# Main.net
KiCad netlist of a schematic drawn in Altium Designer
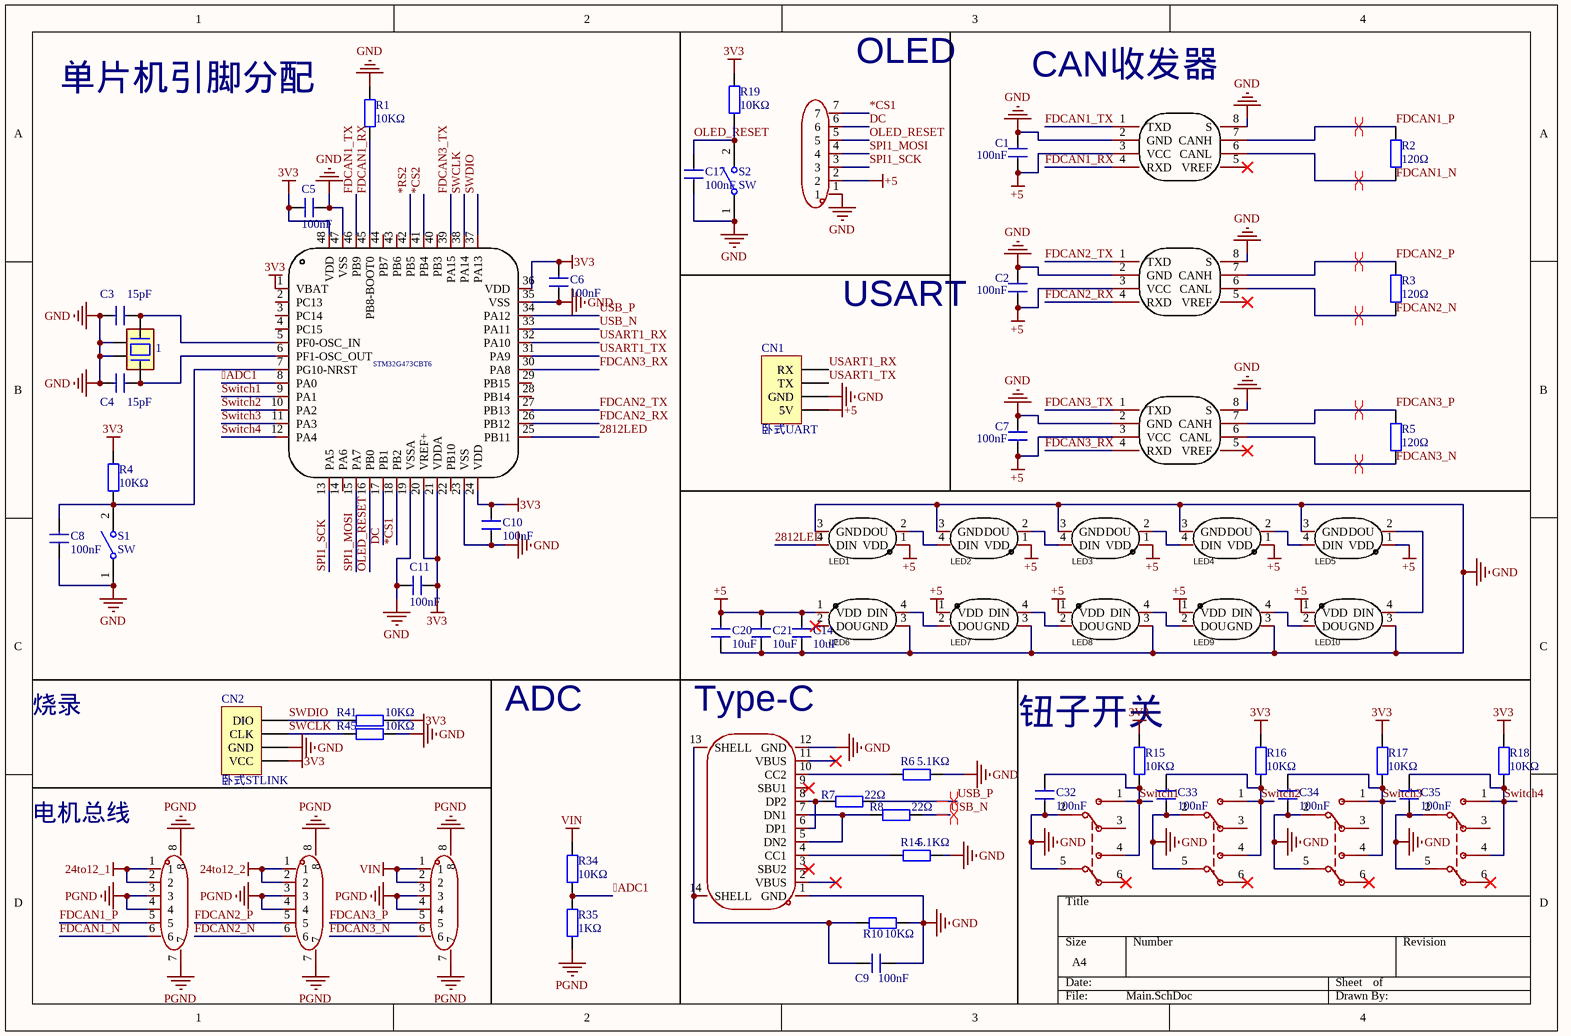
[diagram p0: Main.SchDoc]

(export (version "E")
  (design (tool "Eeschema 10.0.6"))
  (components
    (comp (ref "1")
      (value "3225贴片晶振")
      (footprint "OSC-3225-4P")
      (libsource (lib "Integrated_Library1") (part "3225贴片晶振"))
    )
    (comp (ref "C1")
      (value "100nF")
      (footprint "c0402")
      (description "贴片电容0402")
      (libsource (lib "Integrated_Library1") (part "0402贴片电容"))
    )
    (comp (ref "C2")
      (value "100nF")
      (footprint "c0402")
      (description "贴片电容0402")
      (libsource (lib "Integrated_Library1") (part "0402贴片电容"))
    )
    (comp (ref "C3")
      (value "15pF")
      (footprint "c0402")
      (description "贴片电容0402")
      (libsource (lib "Integrated_Library1") (part "0402贴片电容"))
    )
    (comp (ref "C4")
      (value "15pF")
      (footprint "c0402")
      (description "贴片电容0402")
      (libsource (lib "Integrated_Library1") (part "0402贴片电容"))
    )
    (comp (ref "C5")
      (value "100nF")
      (footprint "c0402")
      (description "贴片电容0402")
      (libsource (lib "Integrated_Library1") (part "0402贴片电容"))
    )
    (comp (ref "C6")
      (value "100nF")
      (footprint "c0402")
      (description "贴片电容0402")
      (libsource (lib "Integrated_Library1") (part "0402贴片电容"))
    )
    (comp (ref "C7")
      (value "100nF")
      (footprint "c0402")
      (description "贴片电容0402")
      (libsource (lib "Integrated_Library1") (part "0402贴片电容"))
    )
    (comp (ref "C8")
      (value "100nF")
      (footprint "c0402")
      (description "贴片电容0402")
      (libsource (lib "Integrated_Library1") (part "0402贴片电容"))
    )
    (comp (ref "C9")
      (value "100nF")
      (footprint "c0402")
      (description "贴片电容0402")
      (libsource (lib "Integrated_Library1") (part "0402贴片电容"))
    )
    (comp (ref "C10")
      (value "100nF")
      (footprint "c0402")
      (description "贴片电容0402")
      (libsource (lib "Integrated_Library1") (part "0402贴片电容"))
    )
    (comp (ref "C11")
      (value "100nF")
      (footprint "c0402")
      (description "贴片电容0402")
      (libsource (lib "Integrated_Library1") (part "0402贴片电容"))
    )
    (comp (ref "C14")
      (value "10uF")
      (footprint "1210")
      (description "1210贴片电容")
      (libsource (lib "Integrated_Library1") (part "1210贴片电容"))
    )
    (comp (ref "C17")
      (value "100nF")
      (footprint "c0402")
      (description "贴片电容0402")
      (libsource (lib "Integrated_Library1") (part "0402贴片电容"))
    )
    (comp (ref "C20")
      (value "10uF")
      (footprint "1210")
      (description "1210贴片电容")
      (libsource (lib "Integrated_Library1") (part "1210贴片电容"))
    )
    (comp (ref "C21")
      (value "10uF")
      (footprint "1210")
      (description "1210贴片电容")
      (libsource (lib "Integrated_Library1") (part "1210贴片电容"))
    )
    (comp (ref "C32")
      (value "100nF")
      (footprint "c0402")
      (description "贴片电容0402")
      (libsource (lib "Integrated_Library1") (part "0402贴片电容"))
    )
    (comp (ref "C33")
      (value "100nF")
      (footprint "c0402")
      (description "贴片电容0402")
      (libsource (lib "Integrated_Library1") (part "0402贴片电容"))
    )
    (comp (ref "C34")
      (value "100nF")
      (footprint "c0402")
      (description "贴片电容0402")
      (libsource (lib "Integrated_Library1") (part "0402贴片电容"))
    )
    (comp (ref "C35")
      (value "100nF")
      (footprint "c0402")
      (description "贴片电容0402")
      (libsource (lib "Integrated_Library1") (part "0402贴片电容"))
    )
    (comp (ref "CN1")
      (value "卧式UART")
      (footprint "CONN-SMD_4P-P1.25_GH1.25-4P")
      (libsource (lib "Integrated_Library1") (part "卧式UART"))
    )
    (comp (ref "CN2")
      (value "卧式STLINK")
      (footprint "CONN-SMD_4P-P1.25_GH1.25-4P")
      (libsource (lib "Integrated_Library1") (part "卧式STLINK"))
    )
    (comp (ref "H1")
      (value "PM254V-11-07-H85")
      (footprint "HDR-TH_7P-P2.54-V-F")
      (fields (field (name "MANUFACTURER") "XFCN(兴飞)"))
      (libsource (lib "Schlib1") (part "PM254V-11-07-H85"))
    )
    (comp (ref "LED1")
      (value "XL-5050RGBC-WS2812B")
      (footprint "LED-SMD_4P-L5.0-W5.0-BL_XL-5050RGBC")
      (description "WS2812B彩灯珠")
      (fields (field (name "MANUFACTURER") "XINGLIGHT(成兴光)"))
      (libsource (lib "RoBoMaster_AllComponent") (part "WS2812B彩灯珠"))
    )
    (comp (ref "LED2")
      (value "XL-5050RGBC-WS2812B")
      (footprint "LED-SMD_4P-L5.0-W5.0-BL_XL-5050RGBC")
      (description "WS2812B彩灯珠")
      (fields (field (name "MANUFACTURER") "XINGLIGHT(成兴光)"))
      (libsource (lib "RoBoMaster_AllComponent") (part "WS2812B彩灯珠"))
    )
    (comp (ref "LED3")
      (value "XL-5050RGBC-WS2812B")
      (footprint "LED-SMD_4P-L5.0-W5.0-BL_XL-5050RGBC")
      (description "WS2812B彩灯珠")
      (fields (field (name "MANUFACTURER") "XINGLIGHT(成兴光)"))
      (libsource (lib "RoBoMaster_AllComponent") (part "WS2812B彩灯珠"))
    )
    (comp (ref "LED4")
      (value "XL-5050RGBC-WS2812B")
      (footprint "LED-SMD_4P-L5.0-W5.0-BL_XL-5050RGBC")
      (description "WS2812B彩灯珠")
      (fields (field (name "MANUFACTURER") "XINGLIGHT(成兴光)"))
      (libsource (lib "RoBoMaster_AllComponent") (part "WS2812B彩灯珠"))
    )
    (comp (ref "LED5")
      (value "XL-5050RGBC-WS2812B")
      (footprint "LED-SMD_4P-L5.0-W5.0-BL_XL-5050RGBC")
      (description "WS2812B彩灯珠")
      (fields (field (name "MANUFACTURER") "XINGLIGHT(成兴光)"))
      (libsource (lib "RoBoMaster_AllComponent") (part "WS2812B彩灯珠"))
    )
    (comp (ref "LED6")
      (value "XL-5050RGBC-WS2812B")
      (footprint "LED-SMD_4P-L5.0-W5.0-BL_XL-5050RGBC")
      (description "WS2812B彩灯珠")
      (fields (field (name "MANUFACTURER") "XINGLIGHT(成兴光)"))
      (libsource (lib "RoBoMaster_AllComponent") (part "WS2812B彩灯珠"))
    )
    (comp (ref "LED7")
      (value "XL-5050RGBC-WS2812B")
      (footprint "LED-SMD_4P-L5.0-W5.0-BL_XL-5050RGBC")
      (description "WS2812B彩灯珠")
      (fields (field (name "MANUFACTURER") "XINGLIGHT(成兴光)"))
      (libsource (lib "RoBoMaster_AllComponent") (part "WS2812B彩灯珠"))
    )
    (comp (ref "LED8")
      (value "XL-5050RGBC-WS2812B")
      (footprint "LED-SMD_4P-L5.0-W5.0-BL_XL-5050RGBC")
      (description "WS2812B彩灯珠")
      (fields (field (name "MANUFACTURER") "XINGLIGHT(成兴光)"))
      (libsource (lib "RoBoMaster_AllComponent") (part "WS2812B彩灯珠"))
    )
    (comp (ref "LED9")
      (value "XL-5050RGBC-WS2812B")
      (footprint "LED-SMD_4P-L5.0-W5.0-BL_XL-5050RGBC")
      (description "WS2812B彩灯珠")
      (fields (field (name "MANUFACTURER") "XINGLIGHT(成兴光)"))
      (libsource (lib "RoBoMaster_AllComponent") (part "WS2812B彩灯珠"))
    )
    (comp (ref "LED10")
      (value "XL-5050RGBC-WS2812B")
      (footprint "LED-SMD_4P-L5.0-W5.0-BL_XL-5050RGBC")
      (description "WS2812B彩灯珠")
      (fields (field (name "MANUFACTURER") "XINGLIGHT(成兴光)"))
      (libsource (lib "RoBoMaster_AllComponent") (part "WS2812B彩灯珠"))
    )
    (comp (ref "R1")
      (value "10KΩ")
      (footprint "R0402")
      (description "0402贴片电阻")
      (libsource (lib "") (part "0402贴片电阻_3"))
    )
    (comp (ref "R2")
      (value "120Ω")
      (footprint "R0402")
      (description "0402贴片电阻")
      (libsource (lib "Integrated_Library1") (part "0402贴片电阻"))
    )
    (comp (ref "R3")
      (value "120Ω")
      (footprint "R0402")
      (description "0402贴片电阻")
      (libsource (lib "Integrated_Library1") (part "0402贴片电阻"))
    )
    (comp (ref "R4")
      (value "10KΩ")
      (footprint "R0402")
      (description "0402贴片电阻")
      (libsource (lib "Integrated_Library1") (part "0402贴片电阻"))
    )
    (comp (ref "R5")
      (value "120Ω")
      (footprint "R0402")
      (description "0402贴片电阻")
      (libsource (lib "Integrated_Library1") (part "0402贴片电阻"))
    )
    (comp (ref "R6")
      (value "5.1KΩ")
      (footprint "R0402")
      (description "0402贴片电阻")
      (libsource (lib "") (part "0402贴片电阻_1"))
    )
    (comp (ref "R7")
      (value "22Ω")
      (footprint "R0402")
      (description "0402贴片电阻")
      (libsource (lib "") (part "0402贴片电阻_1"))
    )
    (comp (ref "R8")
      (value "22Ω")
      (footprint "R0402")
      (description "0402贴片电阻")
      (libsource (lib "") (part "0402贴片电阻_1"))
    )
    (comp (ref "R10")
      (value "10KΩ")
      (footprint "R0402")
      (description "0402贴片电阻")
      (libsource (lib "") (part "0402贴片电阻_1"))
    )
    (comp (ref "R14")
      (value "5.1KΩ")
      (footprint "R0402")
      (description "0402贴片电阻")
      (libsource (lib "") (part "0402贴片电阻_1"))
    )
    (comp (ref "R15")
      (value "10KΩ")
      (footprint "R0402")
      (description "0402贴片电阻")
      (libsource (lib "Integrated_Library1") (part "0402贴片电阻"))
    )
    (comp (ref "R16")
      (value "10KΩ")
      (footprint "R0402")
      (description "0402贴片电阻")
      (libsource (lib "Integrated_Library1") (part "0402贴片电阻"))
    )
    (comp (ref "R17")
      (value "10KΩ")
      (footprint "R0402")
      (description "0402贴片电阻")
      (libsource (lib "Integrated_Library1") (part "0402贴片电阻"))
    )
    (comp (ref "R18")
      (value "10KΩ")
      (footprint "R0402")
      (description "0402贴片电阻")
      (libsource (lib "Integrated_Library1") (part "0402贴片电阻"))
    )
    (comp (ref "R19")
      (value "10KΩ")
      (footprint "R0402")
      (description "0402贴片电阻")
      (libsource (lib "Integrated_Library1") (part "0402贴片电阻"))
    )
    (comp (ref "R34")
      (value "10KΩ")
      (footprint "R0402")
      (description "0402贴片电阻")
      (libsource (lib "") (part "0402贴片电阻_2"))
    )
    (comp (ref "R35")
      (value "1KΩ")
      (footprint "R0402")
      (description "0402贴片电阻")
      (libsource (lib "") (part "0402贴片电阻_2"))
    )
    (comp (ref "R41")
      (value "10KΩ")
      (footprint "R0402")
      (description "0402贴片电阻")
      (libsource (lib "") (part "0402贴片电阻_1"))
    )
    (comp (ref "R45")
      (value "10KΩ")
      (footprint "R0402")
      (description "0402贴片电阻")
      (libsource (lib "") (part "0402贴片电阻_1"))
    )
    (comp (ref "S1")
      (value "SW")
      (footprint "KEY_SMD")
      (description "开关")
      (libsource (lib "Integrated_Library1") (part "SW"))
    )
    (comp (ref "S2")
      (value "SW")
      (footprint "KEY_SMD")
      (description "开关")
      (libsource (lib "Integrated_Library1") (part "SW"))
    )
    (comp (ref "U1")
      (value "ZX-ZH1.5-6PWT")
      (footprint "CONN-SMD_6P-P1.50_ZX-ZH1.5-6PWT")
      (fields (field (name "MANUFACTURER") "Megastar(兆星)"))
      (libsource (lib "Schlib1") (part "ZX-ZH1.5-6PWT"))
    )
    (comp (ref "U2")
      (value "SN65HVD1050DR")
      (footprint "SOIC-8_L4.9-W3.9-P1.27-LS6.0-BL")
      (description "CAN芯片")
      (fields (field (name "MANUFACTURER") "TI(德州仪器)"))
      (libsource (lib "Integrated_Library1") (part "SN65HVD1050DR"))
    )
    (comp (ref "U3")
      (value "ZX-ZH1.5-6PWT")
      (footprint "CONN-SMD_6P-P1.50_ZX-ZH1.5-6PWT")
      (fields (field (name "MANUFACTURER") "Megastar(兆星)"))
      (libsource (lib "Schlib1") (part "ZX-ZH1.5-6PWT"))
    )
    (comp (ref "U4")
      (value "STM32G474CET6")
      (footprint "LQFP-48")
      (fields (field (name "MANUFACTURER") "ST(意法半导体)") (field (name "MANUFACTURER PART") "STM32G473CBT6"))
      (libsource (lib "Integrated_Library1") (part "STM32G474CET6"))
    )
    (comp (ref "U5")
      (value "SN65HVD1050DR")
      (footprint "SOIC-8_L4.9-W3.9-P1.27-LS6.0-BL")
      (description "CAN芯片")
      (fields (field (name "MANUFACTURER") "TI(德州仪器)"))
      (libsource (lib "Integrated_Library1") (part "SN65HVD1050DR"))
    )
    (comp (ref "U6")
      (value "ZX-ZH1.5-6PWT")
      (footprint "CONN-SMD_6P-P1.50_ZX-ZH1.5-6PWT")
      (fields (field (name "MANUFACTURER") "Megastar(兆星)"))
      (libsource (lib "Schlib1") (part "ZX-ZH1.5-6PWT"))
    )
    (comp (ref "U8")
      (value "SN65HVD1050DR")
      (footprint "SOIC-8_L4.9-W3.9-P1.27-LS6.0-BL")
      (description "CAN芯片")
      (fields (field (name "MANUFACTURER") "TI(德州仪器)"))
      (libsource (lib "Integrated_Library1") (part "SN65HVD1050DR"))
    )
    (comp (ref "U9")
      (value "7208P1YZQI")
      (footprint "SW-TH_6P-L12.7-W11.4-P4.70-LS4.8")
      (fields (field (name "MANUFACTURER") "C&K"))
      (libsource (lib "Schlib1") (part "7208P1YZQI"))
    )
    (comp (ref "U10")
      (value "7208P1YZQI")
      (footprint "SW-TH_6P-L12.7-W11.4-P4.70-LS4.8")
      (fields (field (name "MANUFACTURER") "C&K"))
      (libsource (lib "Schlib1") (part "7208P1YZQI"))
    )
    (comp (ref "U11")
      (value "7208P1YZQI")
      (footprint "SW-TH_6P-L12.7-W11.4-P4.70-LS4.8")
      (fields (field (name "MANUFACTURER") "C&K"))
      (libsource (lib "Schlib1") (part "7208P1YZQI"))
    )
    (comp (ref "U12")
      (value "7208P1YZQI")
      (footprint "SW-TH_6P-L12.7-W11.4-P4.70-LS4.8")
      (fields (field (name "MANUFACTURER") "C&K"))
      (libsource (lib "Schlib1") (part "7208P1YZQI"))
    )
    (comp (ref "USB1")
      (value "TYPE-C 16PIN 2MD(073)")
      (footprint "USB-C-SMD_TYPE-C-6PIN-2MD-073")
      (fields (field (name "MANUFACTURER") "SHOU HAN(首韩)"))
      (libsource (lib "Schlib1") (part "TYPE-C 16PIN 2MD(073)"))
    )
  )
  (nets
    (net (code "1") (name "+5") (class "Default")
      (node (ref "C1") (pin "1") (pinfunction "1_1") (pintype "passive"))
      (node (ref "C14") (pin "2") (pinfunction "2_2") (pintype "passive"))
      (node (ref "C2") (pin "1") (pinfunction "1_1") (pintype "passive"))
      (node (ref "C20") (pin "2") (pinfunction "2_2") (pintype "passive"))
      (node (ref "C21") (pin "2") (pinfunction "2_2") (pintype "passive"))
      (node (ref "C7") (pin "1") (pinfunction "1_1") (pintype "passive"))
      (node (ref "CN1") (pin "1") (pinfunction "5V_1") (pintype "passive"))
      (node (ref "H1") (pin "2") (pinfunction "2_2") (pintype "passive"))
      (node (ref "LED1") (pin "1") (pinfunction "VDD_1") (pintype "passive"))
      (node (ref "LED10") (pin "1") (pinfunction "VDD_1") (pintype "passive"))
      (node (ref "LED2") (pin "1") (pinfunction "VDD_1") (pintype "passive"))
      (node (ref "LED3") (pin "1") (pinfunction "VDD_1") (pintype "passive"))
      (node (ref "LED4") (pin "1") (pinfunction "VDD_1") (pintype "passive"))
      (node (ref "LED5") (pin "1") (pinfunction "VDD_1") (pintype "passive"))
      (node (ref "LED6") (pin "1") (pinfunction "VDD_1") (pintype "passive"))
      (node (ref "LED7") (pin "1") (pinfunction "VDD_1") (pintype "passive"))
      (node (ref "LED8") (pin "1") (pinfunction "VDD_1") (pintype "passive"))
      (node (ref "LED9") (pin "1") (pinfunction "VDD_1") (pintype "passive"))
      (node (ref "U2") (pin "3") (pinfunction "VCC_3") (pintype "passive"))
      (node (ref "U5") (pin "3") (pinfunction "VCC_3") (pintype "passive"))
      (node (ref "U8") (pin "3") (pinfunction "VCC_3") (pintype "passive"))
    )
    (net (code "2") (name "/ADC1") (class "Default")
      (node (ref "R34") (pin "1") (pinfunction "1_1") (pintype "passive"))
      (node (ref "R35") (pin "2") (pinfunction "2_2") (pintype "passive"))
      (node (ref "U4") (pin "8") (pinfunction "PA0_8") (pintype "passive"))
    )
    (net (code "3") (name "/*CS1") (class "Default")
      (node (ref "H1") (pin "7") (pinfunction "7_7") (pintype "passive"))
      (node (ref "U4") (pin "18") (pinfunction "PB2_18") (pintype "passive"))
    )
    (net (code "4") (name "/*CS2") (class "Default")
      (node (ref "U4") (pin "41") (pinfunction "PB4_41") (pintype "passive"))
    )
    (net (code "5") (name "/*RS2") (class "Default")
      (node (ref "U4") (pin "42") (pinfunction "PB5_42") (pintype "passive"))
    )
    (net (code "6") (name "/2812LED") (class "Default")
      (node (ref "LED1") (pin "4") (pinfunction "DIN_4") (pintype "passive"))
      (node (ref "U4") (pin "25") (pinfunction "PB11_25") (pintype "passive"))
    )
    (net (code "7") (name "/DC") (class "Default")
      (node (ref "H1") (pin "6") (pinfunction "6_6") (pintype "passive"))
      (node (ref "U4") (pin "17") (pinfunction "PB1_17") (pintype "passive"))
    )
    (net (code "8") (name "/FDCAN1_N") (class "Default")
      (node (ref "R2") (pin "1") (pinfunction "1_1") (pintype "passive"))
      (node (ref "U1") (pin "6") (pinfunction "6_6") (pintype "passive"))
      (node (ref "U2") (pin "6") (pinfunction "CANL_6") (pintype "passive"))
    )
    (net (code "9") (name "/FDCAN1_P") (class "Default")
      (node (ref "R2") (pin "2") (pinfunction "2_2") (pintype "passive"))
      (node (ref "U1") (pin "5") (pinfunction "5_5") (pintype "passive"))
      (node (ref "U2") (pin "7") (pinfunction "CANH_7") (pintype "passive"))
    )
    (net (code "10") (name "/FDCAN1_RX") (class "Default")
      (node (ref "R1") (pin "2") (pinfunction "2_2") (pintype "passive"))
      (node (ref "U2") (pin "4") (pinfunction "RXD_4") (pintype "passive"))
      (node (ref "U4") (pin "45") (pinfunction "PB8-BOOT0_45") (pintype "passive"))
    )
    (net (code "11") (name "/FDCAN1_TX") (class "Default")
      (node (ref "U2") (pin "1") (pinfunction "TXD_1") (pintype "passive"))
      (node (ref "U4") (pin "46") (pinfunction "PB9_46") (pintype "passive"))
    )
    (net (code "12") (name "/FDCAN2_N") (class "Default")
      (node (ref "R3") (pin "1") (pinfunction "1_1") (pintype "passive"))
      (node (ref "U3") (pin "6") (pinfunction "6_6") (pintype "passive"))
      (node (ref "U5") (pin "6") (pinfunction "CANL_6") (pintype "passive"))
    )
    (net (code "13") (name "/FDCAN2_P") (class "Default")
      (node (ref "R3") (pin "2") (pinfunction "2_2") (pintype "passive"))
      (node (ref "U3") (pin "5") (pinfunction "5_5") (pintype "passive"))
      (node (ref "U5") (pin "7") (pinfunction "CANH_7") (pintype "passive"))
    )
    (net (code "14") (name "/FDCAN2_RX") (class "Default")
      (node (ref "U4") (pin "26") (pinfunction "PB12_26") (pintype "passive"))
      (node (ref "U5") (pin "4") (pinfunction "RXD_4") (pintype "passive"))
    )
    (net (code "15") (name "/FDCAN2_TX") (class "Default")
      (node (ref "U4") (pin "27") (pinfunction "PB13_27") (pintype "passive"))
      (node (ref "U5") (pin "1") (pinfunction "TXD_1") (pintype "passive"))
    )
    (net (code "16") (name "/FDCAN3_N") (class "Default")
      (node (ref "R5") (pin "1") (pinfunction "1_1") (pintype "passive"))
      (node (ref "U6") (pin "6") (pinfunction "6_6") (pintype "passive"))
      (node (ref "U8") (pin "6") (pinfunction "CANL_6") (pintype "passive"))
    )
    (net (code "17") (name "/FDCAN3_P") (class "Default")
      (node (ref "R5") (pin "2") (pinfunction "2_2") (pintype "passive"))
      (node (ref "U6") (pin "5") (pinfunction "5_5") (pintype "passive"))
      (node (ref "U8") (pin "7") (pinfunction "CANH_7") (pintype "passive"))
    )
    (net (code "18") (name "/FDCAN3_RX") (class "Default")
      (node (ref "U4") (pin "30") (pinfunction "PA8_30") (pintype "passive"))
      (node (ref "U8") (pin "4") (pinfunction "RXD_4") (pintype "passive"))
    )
    (net (code "19") (name "/FDCAN3_TX") (class "Default")
      (node (ref "U4") (pin "39") (pinfunction "PA15_39") (pintype "passive"))
      (node (ref "U8") (pin "1") (pinfunction "TXD_1") (pintype "passive"))
    )
    (net (code "20") (name "/OLED_RESET") (class "Default")
      (node (ref "C17") (pin "2") (pinfunction "2_2") (pintype "passive"))
      (node (ref "H1") (pin "5") (pinfunction "5_5") (pintype "passive"))
      (node (ref "R19") (pin "1") (pinfunction "1_1") (pintype "passive"))
      (node (ref "S2") (pin "2") (pinfunction "NO_2") (pintype "passive"))
      (node (ref "U4") (pin "16") (pinfunction "PB0_16") (pintype "passive"))
    )
    (net (code "21") (name "/SPI1_MOSI") (class "Default")
      (node (ref "H1") (pin "4") (pinfunction "4_4") (pintype "passive"))
      (node (ref "U4") (pin "15") (pinfunction "PA7_15") (pintype "passive"))
    )
    (net (code "22") (name "/SPI1_SCK") (class "Default")
      (node (ref "H1") (pin "3") (pinfunction "3_3") (pintype "passive"))
      (node (ref "U4") (pin "13") (pinfunction "PA5_13") (pintype "passive"))
    )
    (net (code "23") (name "/SWCLK") (class "Default")
      (node (ref "CN2") (pin "3") (pinfunction "CLK_3") (pintype "passive"))
      (node (ref "R45") (pin "1") (pinfunction "1_1") (pintype "passive"))
      (node (ref "U4") (pin "38") (pinfunction "PA14_38") (pintype "passive"))
    )
    (net (code "24") (name "/SWDIO") (class "Default")
      (node (ref "CN2") (pin "4") (pinfunction "DIO_4") (pintype "passive"))
      (node (ref "R41") (pin "1") (pinfunction "1_1") (pintype "passive"))
      (node (ref "U4") (pin "37") (pinfunction "PA13_37") (pintype "passive"))
    )
    (net (code "25") (name "/Switch1") (class "Default")
      (node (ref "C32") (pin "2") (pinfunction "2_2") (pintype "passive"))
      (node (ref "R15") (pin "1") (pinfunction "1_1") (pintype "passive"))
      (node (ref "U4") (pin "9") (pinfunction "PA1_9") (pintype "passive"))
      (node (ref "U9") (pin "1") (pinfunction "1_1") (pintype "passive"))
      (node (ref "U9") (pin "4") (pinfunction "4_4") (pintype "passive"))
    )
    (net (code "26") (name "/Switch2") (class "Default")
      (node (ref "C33") (pin "2") (pinfunction "2_2") (pintype "passive"))
      (node (ref "R16") (pin "1") (pinfunction "1_1") (pintype "passive"))
      (node (ref "U10") (pin "1") (pinfunction "1_1") (pintype "passive"))
      (node (ref "U10") (pin "4") (pinfunction "4_4") (pintype "passive"))
      (node (ref "U4") (pin "10") (pinfunction "PA2_10") (pintype "passive"))
    )
    (net (code "27") (name "/Switch3") (class "Default")
      (node (ref "C34") (pin "2") (pinfunction "2_2") (pintype "passive"))
      (node (ref "R17") (pin "1") (pinfunction "1_1") (pintype "passive"))
      (node (ref "U11") (pin "1") (pinfunction "1_1") (pintype "passive"))
      (node (ref "U11") (pin "4") (pinfunction "4_4") (pintype "passive"))
      (node (ref "U4") (pin "11") (pinfunction "PA3_11") (pintype "passive"))
    )
    (net (code "28") (name "/Switch4") (class "Default")
      (node (ref "C35") (pin "2") (pinfunction "2_2") (pintype "passive"))
      (node (ref "R18") (pin "1") (pinfunction "1_1") (pintype "passive"))
      (node (ref "U12") (pin "1") (pinfunction "1_1") (pintype "passive"))
      (node (ref "U12") (pin "4") (pinfunction "4_4") (pintype "passive"))
      (node (ref "U4") (pin "12") (pinfunction "PA4_12") (pintype "passive"))
    )
    (net (code "29") (name "/USART1_RX") (class "Default")
      (node (ref "CN1") (pin "4") (pinfunction "RX_4") (pintype "passive"))
      (node (ref "U4") (pin "32") (pinfunction "PA10_32") (pintype "passive"))
    )
    (net (code "30") (name "/USART1_TX") (class "Default")
      (node (ref "CN1") (pin "3") (pinfunction "TX_3") (pintype "passive"))
      (node (ref "U4") (pin "31") (pinfunction "PA9_31") (pintype "passive"))
    )
    (net (code "31") (name "/USB_N") (class "Default")
      (node (ref "R8") (pin "2") (pinfunction "2_2") (pintype "passive"))
      (node (ref "U4") (pin "33") (pinfunction "PA11_33") (pintype "passive"))
    )
    (net (code "32") (name "/USB_P") (class "Default")
      (node (ref "R7") (pin "2") (pinfunction "2_2") (pintype "passive"))
      (node (ref "U4") (pin "34") (pinfunction "PA12_34") (pintype "passive"))
    )
    (net (code "33") (name "3V3") (class "Default")
      (node (ref "C10") (pin "2") (pinfunction "2_2") (pintype "passive"))
      (node (ref "C11") (pin "1") (pinfunction "1_1") (pintype "passive"))
      (node (ref "C5") (pin "2") (pinfunction "2_2") (pintype "passive"))
      (node (ref "C6") (pin "2") (pinfunction "2_2") (pintype "passive"))
      (node (ref "CN2") (pin "1") (pinfunction "VCC_1") (pintype "passive"))
      (node (ref "R15") (pin "2") (pinfunction "2_2") (pintype "passive"))
      (node (ref "R16") (pin "2") (pinfunction "2_2") (pintype "passive"))
      (node (ref "R17") (pin "2") (pinfunction "2_2") (pintype "passive"))
      (node (ref "R18") (pin "2") (pinfunction "2_2") (pintype "passive"))
      (node (ref "R19") (pin "2") (pinfunction "2_2") (pintype "passive"))
      (node (ref "R4") (pin "2") (pinfunction "2_2") (pintype "passive"))
      (node (ref "R41") (pin "2") (pinfunction "2_2") (pintype "passive"))
      (node (ref "U4") (pin "1") (pinfunction "VBAT_1") (pintype "passive"))
      (node (ref "U4") (pin "20") (pinfunction "VREF+_20") (pintype "passive"))
      (node (ref "U4") (pin "21") (pinfunction "VDDA_21") (pintype "passive"))
      (node (ref "U4") (pin "24") (pinfunction "VDD_24") (pintype "passive"))
      (node (ref "U4") (pin "36") (pinfunction "VDD_36") (pintype "passive"))
      (node (ref "U4") (pin "48") (pinfunction "VDD_48") (pintype "passive"))
    )
    (net (code "34") (name "24to12_1") (class "Default")
      (node (ref "U1") (pin "1") (pinfunction "1_1") (pintype "passive"))
      (node (ref "U1") (pin "2") (pinfunction "2_2") (pintype "passive"))
    )
    (net (code "35") (name "24to12_2") (class "Default")
      (node (ref "U3") (pin "1") (pinfunction "1_1") (pintype "passive"))
      (node (ref "U3") (pin "2") (pinfunction "2_2") (pintype "passive"))
    )
    (net (code "36") (name "GND") (class "Default")
      (node (ref "1") (pin "2") (pinfunction "2_2") (pintype "passive"))
      (node (ref "1") (pin "4") (pinfunction "4_4") (pintype "passive"))
      (node (ref "C1") (pin "2") (pinfunction "2_2") (pintype "passive"))
      (node (ref "C10") (pin "1") (pinfunction "1_1") (pintype "passive"))
      (node (ref "C11") (pin "2") (pinfunction "2_2") (pintype "passive"))
      (node (ref "C14") (pin "1") (pinfunction "1_1") (pintype "passive"))
      (node (ref "C17") (pin "1") (pinfunction "1_1") (pintype "passive"))
      (node (ref "C2") (pin "2") (pinfunction "2_2") (pintype "passive"))
      (node (ref "C20") (pin "1") (pinfunction "1_1") (pintype "passive"))
      (node (ref "C21") (pin "1") (pinfunction "1_1") (pintype "passive"))
      (node (ref "C3") (pin "1") (pinfunction "1_1") (pintype "passive"))
      (node (ref "C32") (pin "1") (pinfunction "1_1") (pintype "passive"))
      (node (ref "C33") (pin "1") (pinfunction "1_1") (pintype "passive"))
      (node (ref "C34") (pin "1") (pinfunction "1_1") (pintype "passive"))
      (node (ref "C35") (pin "1") (pinfunction "1_1") (pintype "passive"))
      (node (ref "C4") (pin "1") (pinfunction "1_1") (pintype "passive"))
      (node (ref "C5") (pin "1") (pinfunction "1_1") (pintype "passive"))
      (node (ref "C6") (pin "1") (pinfunction "1_1") (pintype "passive"))
      (node (ref "C7") (pin "2") (pinfunction "2_2") (pintype "passive"))
      (node (ref "C8") (pin "1") (pinfunction "1_1") (pintype "passive"))
      (node (ref "C9") (pin "2") (pinfunction "2_2") (pintype "passive"))
      (node (ref "CN1") (pin "2") (pinfunction "GND_2") (pintype "passive"))
      (node (ref "CN2") (pin "2") (pinfunction "GND_2") (pintype "passive"))
      (node (ref "H1") (pin "1") (pinfunction "1_1") (pintype "passive"))
      (node (ref "LED1") (pin "3") (pinfunction "GND_3") (pintype "passive"))
      (node (ref "LED10") (pin "3") (pinfunction "GND_3") (pintype "passive"))
      (node (ref "LED2") (pin "3") (pinfunction "GND_3") (pintype "passive"))
      (node (ref "LED3") (pin "3") (pinfunction "GND_3") (pintype "passive"))
      (node (ref "LED4") (pin "3") (pinfunction "GND_3") (pintype "passive"))
      (node (ref "LED5") (pin "3") (pinfunction "GND_3") (pintype "passive"))
      (node (ref "LED6") (pin "3") (pinfunction "GND_3") (pintype "passive"))
      (node (ref "LED7") (pin "3") (pinfunction "GND_3") (pintype "passive"))
      (node (ref "LED8") (pin "3") (pinfunction "GND_3") (pintype "passive"))
      (node (ref "LED9") (pin "3") (pinfunction "GND_3") (pintype "passive"))
      (node (ref "R1") (pin "1") (pinfunction "1_1") (pintype "passive"))
      (node (ref "R10") (pin "2") (pinfunction "2_2") (pintype "passive"))
      (node (ref "R14") (pin "2") (pinfunction "2_2") (pintype "passive"))
      (node (ref "R45") (pin "2") (pinfunction "2_2") (pintype "passive"))
      (node (ref "R6") (pin "2") (pinfunction "2_2") (pintype "passive"))
      (node (ref "S1") (pin "1") (pinfunction "COMMON_1") (pintype "passive"))
      (node (ref "S2") (pin "1") (pinfunction "COMMON_1") (pintype "passive"))
      (node (ref "U10") (pin "2") (pinfunction "2_2") (pintype "passive"))
      (node (ref "U10") (pin "5") (pinfunction "5_5") (pintype "passive"))
      (node (ref "U11") (pin "2") (pinfunction "2_2") (pintype "passive"))
      (node (ref "U11") (pin "5") (pinfunction "5_5") (pintype "passive"))
      (node (ref "U12") (pin "2") (pinfunction "2_2") (pintype "passive"))
      (node (ref "U12") (pin "5") (pinfunction "5_5") (pintype "passive"))
      (node (ref "U2") (pin "2") (pinfunction "GND_2") (pintype "passive"))
      (node (ref "U2") (pin "8") (pinfunction "S_8") (pintype "passive"))
      (node (ref "U4") (pin "19") (pinfunction "VSSA_19") (pintype "passive"))
      (node (ref "U4") (pin "23") (pinfunction "VSS_23") (pintype "passive"))
      (node (ref "U4") (pin "35") (pinfunction "VSS_35") (pintype "passive"))
      (node (ref "U4") (pin "47") (pinfunction "VSS_47") (pintype "passive"))
      (node (ref "U5") (pin "2") (pinfunction "GND_2") (pintype "passive"))
      (node (ref "U5") (pin "8") (pinfunction "S_8") (pintype "passive"))
      (node (ref "U8") (pin "2") (pinfunction "GND_2") (pintype "passive"))
      (node (ref "U8") (pin "8") (pinfunction "S_8") (pintype "passive"))
      (node (ref "U9") (pin "2") (pinfunction "2_2") (pintype "passive"))
      (node (ref "U9") (pin "5") (pinfunction "5_5") (pintype "passive"))
      (node (ref "USB1") (pin "1") (pinfunction "GND_1") (pintype "passive"))
      (node (ref "USB1") (pin "12") (pinfunction "GND_12") (pintype "passive"))
    )
    (net (code "37") (name "Net-(C9-Pad1)") (class "Default")
      (node (ref "C9") (pin "1") (pinfunction "1_1") (pintype "passive"))
      (node (ref "R10") (pin "1") (pinfunction "1_1") (pintype "passive"))
      (node (ref "USB1") (pin "13") (pinfunction "SHELL_13") (pintype "passive"))
      (node (ref "USB1") (pin "14") (pinfunction "SHELL_14") (pintype "passive"))
    )
    (net (code "38") (name "Net-(LED1-DOU)") (class "Default")
      (node (ref "LED1") (pin "2") (pinfunction "DOU_2") (pintype "passive"))
      (node (ref "LED2") (pin "4") (pinfunction "DIN_4") (pintype "passive"))
    )
    (net (code "39") (name "Net-(LED2-DOU)") (class "Default")
      (node (ref "LED2") (pin "2") (pinfunction "DOU_2") (pintype "passive"))
      (node (ref "LED3") (pin "4") (pinfunction "DIN_4") (pintype "passive"))
    )
    (net (code "40") (name "Net-(LED3-DOU)") (class "Default")
      (node (ref "LED3") (pin "2") (pinfunction "DOU_2") (pintype "passive"))
      (node (ref "LED4") (pin "4") (pinfunction "DIN_4") (pintype "passive"))
    )
    (net (code "41") (name "Net-(LED4-DOU)") (class "Default")
      (node (ref "LED4") (pin "2") (pinfunction "DOU_2") (pintype "passive"))
      (node (ref "LED5") (pin "4") (pinfunction "DIN_4") (pintype "passive"))
    )
    (net (code "42") (name "Net-(LED6-DIN)") (class "Default")
      (node (ref "LED6") (pin "4") (pinfunction "DIN_4") (pintype "passive"))
      (node (ref "LED7") (pin "2") (pinfunction "DOU_2") (pintype "passive"))
    )
    (net (code "43") (name "Net-(LED7-DIN)") (class "Default")
      (node (ref "LED7") (pin "4") (pinfunction "DIN_4") (pintype "passive"))
      (node (ref "LED8") (pin "2") (pinfunction "DOU_2") (pintype "passive"))
    )
    (net (code "44") (name "Net-(LED8-DIN)") (class "Default")
      (node (ref "LED8") (pin "4") (pinfunction "DIN_4") (pintype "passive"))
      (node (ref "LED9") (pin "2") (pinfunction "DOU_2") (pintype "passive"))
    )
    (net (code "45") (name "Net-(LED10-DIN)") (class "Default")
      (node (ref "LED10") (pin "4") (pinfunction "DIN_4") (pintype "passive"))
      (node (ref "LED5") (pin "2") (pinfunction "DOU_2") (pintype "passive"))
    )
    (net (code "46") (name "Net-(LED10-DOU)") (class "Default")
      (node (ref "LED10") (pin "2") (pinfunction "DOU_2") (pintype "passive"))
      (node (ref "LED9") (pin "4") (pinfunction "DIN_4") (pintype "passive"))
    )
    (net (code "47") (name "Net-(S1-NO)") (class "Default")
      (node (ref "C8") (pin "2") (pinfunction "2_2") (pintype "passive"))
      (node (ref "R4") (pin "1") (pinfunction "1_1") (pintype "passive"))
      (node (ref "S1") (pin "2") (pinfunction "NO_2") (pintype "passive"))
      (node (ref "U4") (pin "7") (pinfunction "PG10-NRST_7") (pintype "passive"))
    )
    (net (code "48") (name "Net-(U4-PF0-OSC_IN)") (class "Default")
      (node (ref "1") (pin "3") (pinfunction "3_3") (pintype "passive"))
      (node (ref "C3") (pin "2") (pinfunction "2_2") (pintype "passive"))
      (node (ref "U4") (pin "5") (pinfunction "PF0-OSC_IN_5") (pintype "passive"))
    )
    (net (code "49") (name "Net-(U4-PF1-OSC_OUT)") (class "Default")
      (node (ref "1") (pin "1") (pinfunction "1_1") (pintype "passive"))
      (node (ref "C4") (pin "2") (pinfunction "2_2") (pintype "passive"))
      (node (ref "U4") (pin "6") (pinfunction "PF1-OSC_OUT_6") (pintype "passive"))
    )
    (net (code "50") (name "Net-(USB1-CC1)") (class "Default")
      (node (ref "R14") (pin "1") (pinfunction "1_1") (pintype "passive"))
      (node (ref "USB1") (pin "4") (pinfunction "CC1_4") (pintype "passive"))
    )
    (net (code "51") (name "Net-(USB1-CC2)") (class "Default")
      (node (ref "R6") (pin "1") (pinfunction "1_1") (pintype "passive"))
      (node (ref "USB1") (pin "10") (pinfunction "CC2_10") (pintype "passive"))
    )
    (net (code "52") (name "Net-(USB1-DN1)") (class "Default")
      (node (ref "R8") (pin "1") (pinfunction "1_1") (pintype "passive"))
      (node (ref "USB1") (pin "5") (pinfunction "DN2_5") (pintype "passive"))
      (node (ref "USB1") (pin "7") (pinfunction "DN1_7") (pintype "passive"))
    )
    (net (code "53") (name "Net-(USB1-DP1)") (class "Default")
      (node (ref "R7") (pin "1") (pinfunction "1_1") (pintype "passive"))
      (node (ref "USB1") (pin "6") (pinfunction "DP1_6") (pintype "passive"))
      (node (ref "USB1") (pin "8") (pinfunction "DP2_8") (pintype "passive"))
    )
    (net (code "54") (name "PGND") (class "Default")
      (node (ref "R35") (pin "1") (pinfunction "1_1") (pintype "passive"))
      (node (ref "U1") (pin "3") (pinfunction "3_3") (pintype "passive"))
      (node (ref "U1") (pin "4") (pinfunction "4_4") (pintype "passive"))
      (node (ref "U1") (pin "7") (pinfunction "7_7") (pintype "passive"))
      (node (ref "U1") (pin "8") (pinfunction "8_8") (pintype "passive"))
      (node (ref "U3") (pin "3") (pinfunction "3_3") (pintype "passive"))
      (node (ref "U3") (pin "4") (pinfunction "4_4") (pintype "passive"))
      (node (ref "U3") (pin "7") (pinfunction "7_7") (pintype "passive"))
      (node (ref "U3") (pin "8") (pinfunction "8_8") (pintype "passive"))
      (node (ref "U6") (pin "3") (pinfunction "3_3") (pintype "passive"))
      (node (ref "U6") (pin "4") (pinfunction "4_4") (pintype "passive"))
      (node (ref "U6") (pin "7") (pinfunction "7_7") (pintype "passive"))
      (node (ref "U6") (pin "8") (pinfunction "8_8") (pintype "passive"))
    )
    (net (code "55") (name "VIN") (class "Default")
      (node (ref "R34") (pin "2") (pinfunction "2_2") (pintype "passive"))
      (node (ref "U6") (pin "1") (pinfunction "1_1") (pintype "passive"))
      (node (ref "U6") (pin "2") (pinfunction "2_2") (pintype "passive"))
    )
    (net (code "56") (name "unconnected-(LED6-DOU-Pad2)") (class "Default")
      (node (ref "LED6") (pin "2") (pinfunction "DOU_2") (pintype "passive+no_connect"))
    )
    (net (code "57") (name "unconnected-(U2-VREF-Pad5)") (class "Default")
      (node (ref "U2") (pin "5") (pinfunction "VREF_5") (pintype "passive+no_connect"))
    )
    (net (code "58") (name "unconnected-(U4-PA6-Pad14)") (class "Default")
      (node (ref "U4") (pin "14") (pinfunction "PA6_14") (pintype "passive"))
    )
    (net (code "59") (name "unconnected-(U4-PB3-Pad40)") (class "Default")
      (node (ref "U4") (pin "40") (pinfunction "PB3_40") (pintype "passive"))
    )
    (net (code "60") (name "unconnected-(U4-PB6-Pad43)") (class "Default")
      (node (ref "U4") (pin "43") (pinfunction "PB6_43") (pintype "passive"))
    )
    (net (code "61") (name "unconnected-(U4-PB7-Pad44)") (class "Default")
      (node (ref "U4") (pin "44") (pinfunction "PB7_44") (pintype "passive"))
    )
    (net (code "62") (name "unconnected-(U4-PB10-Pad22)") (class "Default")
      (node (ref "U4") (pin "22") (pinfunction "PB10_22") (pintype "passive"))
    )
    (net (code "63") (name "unconnected-(U4-PB14-Pad28)") (class "Default")
      (node (ref "U4") (pin "28") (pinfunction "PB14_28") (pintype "passive"))
    )
    (net (code "64") (name "unconnected-(U4-PB15-Pad29)") (class "Default")
      (node (ref "U4") (pin "29") (pinfunction "PB15_29") (pintype "passive"))
    )
    (net (code "65") (name "unconnected-(U4-PC13-Pad2)") (class "Default")
      (node (ref "U4") (pin "2") (pinfunction "PC13_2") (pintype "passive"))
    )
    (net (code "66") (name "unconnected-(U4-PC14-Pad3)") (class "Default")
      (node (ref "U4") (pin "3") (pinfunction "PC14_3") (pintype "passive"))
    )
    (net (code "67") (name "unconnected-(U4-PC15-Pad4)") (class "Default")
      (node (ref "U4") (pin "4") (pinfunction "PC15_4") (pintype "passive"))
    )
    (net (code "68") (name "unconnected-(U5-VREF-Pad5)") (class "Default")
      (node (ref "U5") (pin "5") (pinfunction "VREF_5") (pintype "passive+no_connect"))
    )
    (net (code "69") (name "unconnected-(U8-VREF-Pad5)") (class "Default")
      (node (ref "U8") (pin "5") (pinfunction "VREF_5") (pintype "passive+no_connect"))
    )
    (net (code "70") (name "unconnected-(U9-Pad3)") (class "Default")
      (node (ref "U9") (pin "3") (pinfunction "3_3") (pintype "passive"))
    )
    (net (code "71") (name "unconnected-(U9-Pad6)") (class "Default")
      (node (ref "U9") (pin "6") (pinfunction "6_6") (pintype "passive+no_connect"))
    )
    (net (code "72") (name "unconnected-(U10-Pad3)") (class "Default")
      (node (ref "U10") (pin "3") (pinfunction "3_3") (pintype "passive"))
    )
    (net (code "73") (name "unconnected-(U10-Pad6)") (class "Default")
      (node (ref "U10") (pin "6") (pinfunction "6_6") (pintype "passive+no_connect"))
    )
    (net (code "74") (name "unconnected-(U11-Pad3)") (class "Default")
      (node (ref "U11") (pin "3") (pinfunction "3_3") (pintype "passive"))
    )
    (net (code "75") (name "unconnected-(U11-Pad6)") (class "Default")
      (node (ref "U11") (pin "6") (pinfunction "6_6") (pintype "passive+no_connect"))
    )
    (net (code "76") (name "unconnected-(U12-Pad3)") (class "Default")
      (node (ref "U12") (pin "3") (pinfunction "3_3") (pintype "passive"))
    )
    (net (code "77") (name "unconnected-(U12-Pad6)") (class "Default")
      (node (ref "U12") (pin "6") (pinfunction "6_6") (pintype "passive+no_connect"))
    )
    (net (code "78") (name "unconnected-(USB1-SBU1-Pad9)") (class "Default")
      (node (ref "USB1") (pin "9") (pinfunction "SBU1_9") (pintype "passive+no_connect"))
    )
    (net (code "79") (name "unconnected-(USB1-SBU2-Pad3)") (class "Default")
      (node (ref "USB1") (pin "3") (pinfunction "SBU2_3") (pintype "passive+no_connect"))
    )
    (net (code "80") (name "unconnected-(USB1-VBUS-Pad2)") (class "Default")
      (node (ref "USB1") (pin "2") (pinfunction "VBUS_2") (pintype "passive+no_connect"))
    )
    (net (code "81") (name "unconnected-(USB1-VBUS-Pad11)") (class "Default")
      (node (ref "USB1") (pin "11") (pinfunction "VBUS_11") (pintype "passive+no_connect"))
    )
  )
)
